# sheet3.net
KiCad netlist of a schematic drawn in Altium Designer
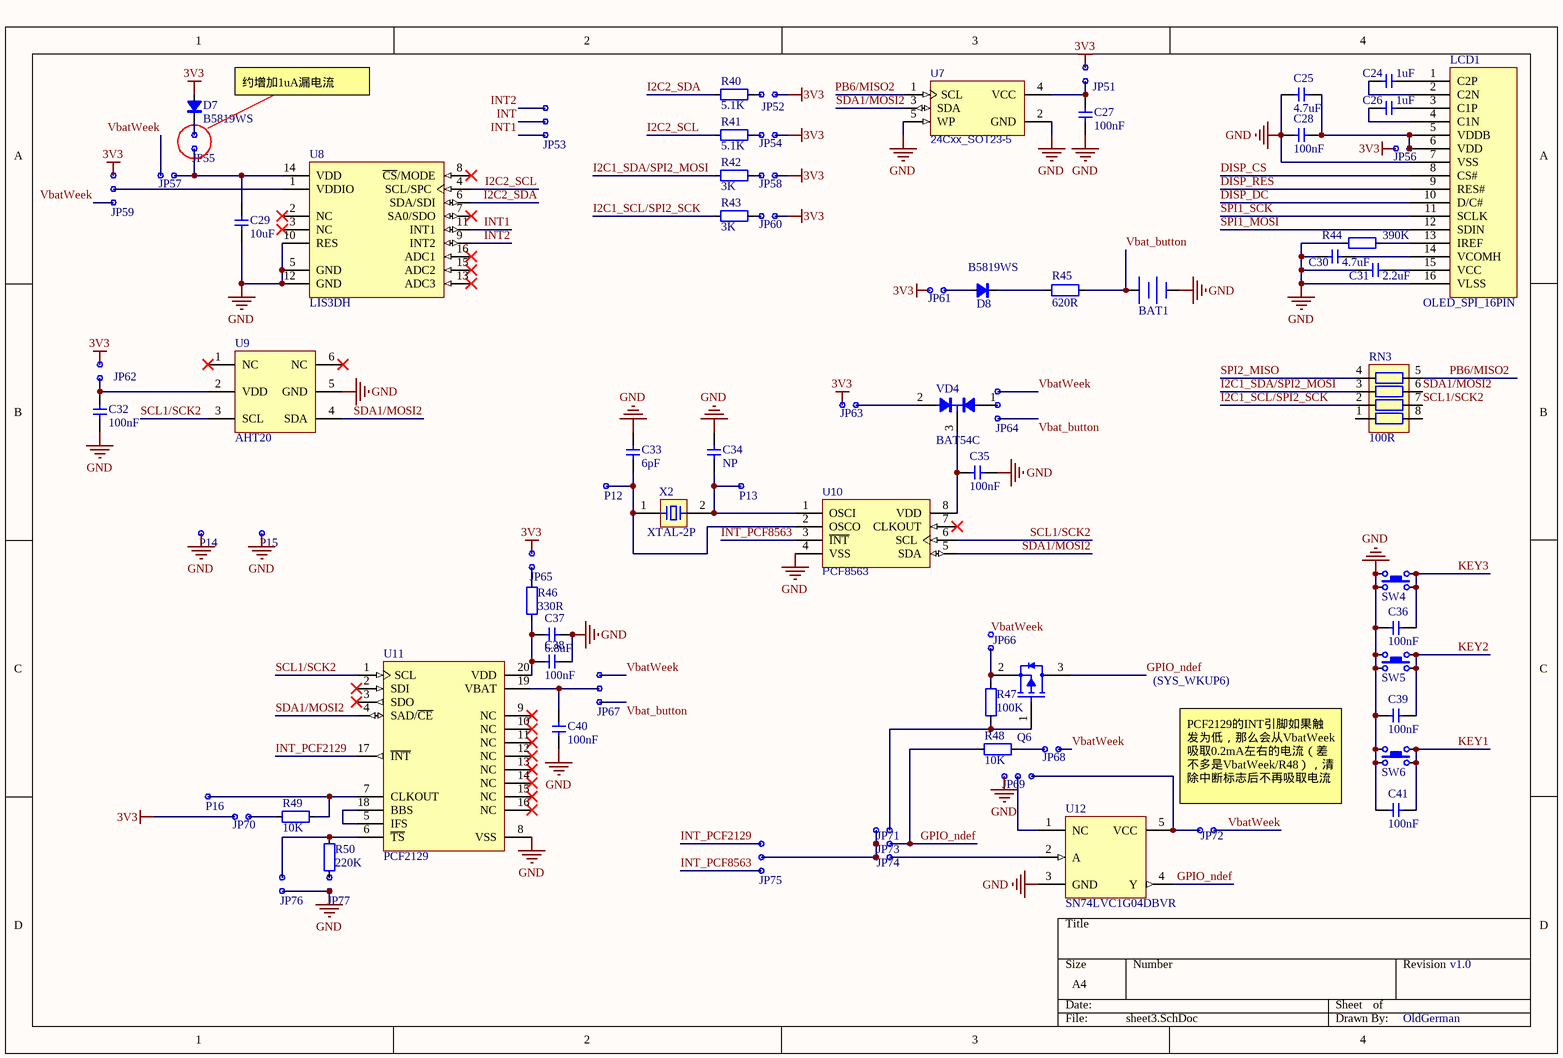
[diagram p0: sheet3.SchDoc]

(export (version "E")
  (design (tool "Eeschema 10.0.6"))
  (components
    (comp (ref "BAT1")
      (value "BAT")
      (footprint "MS621FE-FL11E")
      (description "锂电池")
      (libsource (lib "ODG_AD_Lib") (part "BAT"))
    )
    (comp (ref "C24")
      (value "1uF")
      (footprint "C0603")
      (description "Capacitor")
      (libsource (lib "ODG_AD_Lib") (part "CAP"))
    )
    (comp (ref "C25")
      (value "4.7uF")
      (footprint "C0603")
      (description "Capacitor")
      (libsource (lib "ODG_AD_Lib") (part "CAP"))
    )
    (comp (ref "C26")
      (value "1uF")
      (footprint "C0603")
      (description "Capacitor")
      (libsource (lib "ODG_AD_Lib") (part "CAP"))
    )
    (comp (ref "C27")
      (value "100nF")
      (footprint "C0603")
      (description "Capacitor")
      (libsource (lib "ODG_AD_Lib") (part "CAP"))
    )
    (comp (ref "C28")
      (value "100nF")
      (footprint "C0603")
      (description "Capacitor")
      (libsource (lib "ODG_AD_Lib") (part "CAP"))
    )
    (comp (ref "C29")
      (value "10uF")
      (footprint "C0603")
      (description "Capacitor")
      (libsource (lib "ODG_AD_Lib") (part "CAP"))
    )
    (comp (ref "C30")
      (value "4.7uF")
      (footprint "C0603")
      (description "Capacitor")
      (libsource (lib "ODG_AD_Lib") (part "CAP"))
    )
    (comp (ref "C31")
      (value "2.2uF")
      (footprint "C0603")
      (description "Capacitor")
      (libsource (lib "ODG_AD_Lib") (part "CAP"))
    )
    (comp (ref "C32")
      (value "100nF")
      (footprint "C0603")
      (description "Capacitor")
      (libsource (lib "ODG_AD_Lib") (part "CAP"))
    )
    (comp (ref "C33")
      (value "6pF")
      (footprint "C0603")
      (description "Capacitor")
      (libsource (lib "ODG_AD_Lib") (part "CAP"))
    )
    (comp (ref "C34")
      (value "NP")
      (footprint "C0603")
      (description "Capacitor")
      (libsource (lib "ODG_AD_Lib") (part "CAP"))
    )
    (comp (ref "C35")
      (value "100nF")
      (footprint "C0603")
      (description "Capacitor")
      (libsource (lib "ODG_AD_Lib") (part "CAP"))
    )
    (comp (ref "C36")
      (value "100nF")
      (footprint "C0603")
      (description "Capacitor")
      (libsource (lib "ODG_AD_Lib") (part "CAP"))
    )
    (comp (ref "C37")
      (value "6.8uF")
      (footprint "C0603")
      (description "Capacitor")
      (libsource (lib "ODG_AD_Lib") (part "CAP"))
    )
    (comp (ref "C38")
      (value "100nF")
      (footprint "C0603")
      (description "Capacitor")
      (libsource (lib "ODG_AD_Lib") (part "CAP"))
    )
    (comp (ref "C39")
      (value "100nF")
      (footprint "C0603")
      (description "Capacitor")
      (libsource (lib "ODG_AD_Lib") (part "CAP"))
    )
    (comp (ref "C40")
      (value "100nF")
      (footprint "C0603")
      (description "Capacitor")
      (libsource (lib "ODG_AD_Lib") (part "CAP"))
    )
    (comp (ref "C41")
      (value "100nF")
      (footprint "C0603")
      (description "Capacitor")
      (libsource (lib "ODG_AD_Lib") (part "CAP"))
    )
    (comp (ref "D7")
      (value "B5819WS")
      (footprint "SOD-323")
      (description "二极管")
      (libsource (lib "") (part "DIODE_1"))
    )
    (comp (ref "D8")
      (value "B5819WS")
      (footprint "SOD-323")
      (description "二极管")
      (libsource (lib "ODG_AD_Lib") (part "DIODE"))
    )
    (comp (ref "JP51")
      (value "CONN_X2_DOT")
      (footprint "2.54mm_Male_x2")
      (libsource (lib "ODG_AD_Lib") (part "CONN_X2_DOT"))
    )
    (comp (ref "JP52")
      (value "CONN_X2_DOT")
      (footprint "2.54mm_Male_x2")
      (libsource (lib "ODG_AD_Lib") (part "CONN_X2_DOT"))
    )
    (comp (ref "JP53")
      (value "CONN_X3_DOT")
      (footprint "2.54mm_Male_x3")
      (libsource (lib "ODG_AD_Lib") (part "CONN_X3_DOT"))
    )
    (comp (ref "JP54")
      (value "CONN_X2_DOT")
      (footprint "2.54mm_Male_x2")
      (libsource (lib "ODG_AD_Lib") (part "CONN_X2_DOT"))
    )
    (comp (ref "JP55")
      (value "CONN_X2_DOT")
      (footprint "2.54mm_Male_x2")
      (libsource (lib "ODG_AD_Lib") (part "CONN_X2_DOT"))
    )
    (comp (ref "JP56")
      (value "CONN_X2_DOT")
      (footprint "2.54mm_Male_x2")
      (libsource (lib "ODG_AD_Lib") (part "CONN_X2_DOT"))
    )
    (comp (ref "JP57")
      (value "CONN_X2_DOT")
      (footprint "2.54mm_Male_x2")
      (libsource (lib "ODG_AD_Lib") (part "CONN_X2_DOT"))
    )
    (comp (ref "JP58")
      (value "CONN_X2_DOT")
      (footprint "2.54mm_Male_x2")
      (libsource (lib "ODG_AD_Lib") (part "CONN_X2_DOT"))
    )
    (comp (ref "JP59")
      (value "CONN_X3_DOT")
      (footprint "2.54mm_Male_x3")
      (libsource (lib "ODG_AD_Lib") (part "CONN_X3_DOT"))
    )
    (comp (ref "JP60")
      (value "CONN_X2_DOT")
      (footprint "2.54mm_Male_x2")
      (libsource (lib "ODG_AD_Lib") (part "CONN_X2_DOT"))
    )
    (comp (ref "JP61")
      (value "CONN_X2_DOT")
      (footprint "2.54mm_Male_x2")
      (libsource (lib "ODG_AD_Lib") (part "CONN_X2_DOT"))
    )
    (comp (ref "JP62")
      (value "CONN_X2_DOT")
      (footprint "2.54mm_Male_x2")
      (libsource (lib "ODG_AD_Lib") (part "CONN_X2_DOT"))
    )
    (comp (ref "JP63")
      (value "CONN_X2_DOT")
      (footprint "2.54mm_Male_x2")
      (libsource (lib "ODG_AD_Lib") (part "CONN_X2_DOT"))
    )
    (comp (ref "JP64")
      (value "CONN_X3_DOT")
      (footprint "2.54mm_Male_x3")
      (libsource (lib "ODG_AD_Lib") (part "CONN_X3_DOT"))
    )
    (comp (ref "JP65")
      (value "CONN_X2_DOT")
      (footprint "2.54mm_Male_x2")
      (libsource (lib "ODG_AD_Lib") (part "CONN_X2_DOT"))
    )
    (comp (ref "JP66")
      (value "CONN_X2_DOT")
      (footprint "2.54mm_Male_x2")
      (libsource (lib "ODG_AD_Lib") (part "CONN_X2_DOT"))
    )
    (comp (ref "JP67")
      (value "CONN_X3_DOT")
      (footprint "2.54mm_Male_x3")
      (libsource (lib "ODG_AD_Lib") (part "CONN_X3_DOT"))
    )
    (comp (ref "JP68")
      (value "CONN_X2_DOT")
      (footprint "2.54mm_Male_x2")
      (libsource (lib "ODG_AD_Lib") (part "CONN_X2_DOT"))
    )
    (comp (ref "JP69")
      (value "CONN_X3_DOT")
      (footprint "2.54mm_Male_x3")
      (libsource (lib "ODG_AD_Lib") (part "CONN_X3_DOT"))
    )
    (comp (ref "JP70")
      (value "CONN_X2_DOT")
      (footprint "2.54mm_Male_x2")
      (libsource (lib "ODG_AD_Lib") (part "CONN_X2_DOT"))
    )
    (comp (ref "JP71")
      (value "CONN_X2_DOT")
      (footprint "2.54mm_Male_x2")
      (libsource (lib "ODG_AD_Lib") (part "CONN_X2_DOT"))
    )
    (comp (ref "JP72")
      (value "CONN_X2_DOT")
      (footprint "2.54mm_Male_x2")
      (libsource (lib "ODG_AD_Lib") (part "CONN_X2_DOT"))
    )
    (comp (ref "JP73")
      (value "CONN_X2_DOT")
      (footprint "2.54mm_Male_x2")
      (libsource (lib "ODG_AD_Lib") (part "CONN_X2_DOT"))
    )
    (comp (ref "JP74")
      (value "CONN_X2_DOT")
      (footprint "2.54mm_Male_x2")
      (libsource (lib "ODG_AD_Lib") (part "CONN_X2_DOT"))
    )
    (comp (ref "JP75")
      (value "CONN_X3_DOT")
      (footprint "2.54mm_Male_x3")
      (libsource (lib "ODG_AD_Lib") (part "CONN_X3_DOT"))
    )
    (comp (ref "JP76")
      (value "CONN_X2_DOT")
      (footprint "2.54mm_Male_x2")
      (libsource (lib "ODG_AD_Lib") (part "CONN_X2_DOT"))
    )
    (comp (ref "JP77")
      (value "CONN_X2_DOT")
      (footprint "2.54mm_Male_x2")
      (libsource (lib "ODG_AD_Lib") (part "CONN_X2_DOT"))
    )
    (comp (ref "LCD1")
      (value "OLED_SPI_16PIN")
      (footprint "oled_64x48_0.66_SSD1306_TOP_straight_no_3d")
      (libsource (lib "ODG_AD_Lib") (part "OLED_SPI_16PIN"))
    )
    (comp (ref "P12")
      (value "CONN_X1_DOT")
      (footprint "2.54mm_Male_x1")
      (libsource (lib "ODG_AD_Lib") (part "CONN_X1_DOT"))
    )
    (comp (ref "P13")
      (value "CONN_X1_DOT")
      (footprint "2.54mm_Male_x1")
      (libsource (lib "ODG_AD_Lib") (part "CONN_X1_DOT"))
    )
    (comp (ref "P14")
      (value "CONN_X1_DOT")
      (footprint "2.54mm_Male_x1")
      (libsource (lib "ODG_AD_Lib") (part "CONN_X1_DOT"))
    )
    (comp (ref "P15")
      (value "CONN_X1_DOT")
      (footprint "2.54mm_Male_x1")
      (libsource (lib "ODG_AD_Lib") (part "CONN_X1_DOT"))
    )
    (comp (ref "P16")
      (value "CONN_X1_DOT")
      (footprint "2.54mm_Male_x1")
      (libsource (lib "ODG_AD_Lib") (part "CONN_X1_DOT"))
    )
    (comp (ref "Q6")
      (value "P-MOS")
      (footprint "INFINEON SOT-23-3")
      (libsource (lib "ODG_AD_Lib") (part "P-MOS_123"))
    )
    (comp (ref "R40")
      (value "5.1K")
      (footprint "R0603")
      (description "Resistor")
      (libsource (lib "") (part "RES_1"))
    )
    (comp (ref "R41")
      (value "5.1K")
      (footprint "R0603")
      (description "Resistor")
      (libsource (lib "") (part "RES_1"))
    )
    (comp (ref "R42")
      (value "3K")
      (footprint "R0603")
      (description "Resistor")
      (libsource (lib "") (part "RES_1"))
    )
    (comp (ref "R43")
      (value "3K")
      (footprint "R0603")
      (description "Resistor")
      (libsource (lib "") (part "RES_1"))
    )
    (comp (ref "R44")
      (value "390K")
      (footprint "R0603")
      (description "Resistor")
      (libsource (lib "") (part "RES_2"))
    )
    (comp (ref "R45")
      (value "620R")
      (footprint "R0603")
      (description "Resistor")
      (libsource (lib "") (part "RES_2"))
    )
    (comp (ref "R46")
      (value "330R")
      (footprint "R0603")
      (description "Resistor")
      (libsource (lib "") (part "RES_3"))
    )
    (comp (ref "R47")
      (value "100K")
      (footprint "R0603")
      (description "Resistor")
      (libsource (lib "") (part "RES_2"))
    )
    (comp (ref "R48")
      (value "10K")
      (footprint "R0603")
      (description "Resistor")
      (libsource (lib "") (part "RES_1"))
    )
    (comp (ref "R49")
      (value "10K")
      (footprint "R0603")
      (description "Resistor")
      (libsource (lib "ODG_AD_Lib") (part "RES"))
    )
    (comp (ref "R50")
      (value "220K")
      (footprint "R0603")
      (description "Resistor")
      (libsource (lib "") (part "RES_3"))
    )
    (comp (ref "RN3")
      (value "100R")
      (footprint "RESNET 1206-8 CONCAVE")
      (description "贴片网络排阻")
      (fields (field (name "版权归属") "源创客"))
      (libsource (lib "ODG_AD_Lib") (part "RES-8P4R"))
    )
    (comp (ref "SW4")
      (value "Button-4P")
      (footprint "SWITCH_3X4X2.5_4PIN_SMD")
      (description "Button")
      (libsource (lib "ODG_AD_Lib") (part "Button-4P"))
    )
    (comp (ref "SW5")
      (value "Button-4P")
      (footprint "SWITCH_3X4X2.5_4PIN_SMD")
      (description "Button")
      (libsource (lib "ODG_AD_Lib") (part "Button-4P"))
    )
    (comp (ref "SW6")
      (value "Button-4P")
      (footprint "SWITCH_3X4X2.5_4PIN_SMD")
      (description "Button")
      (libsource (lib "ODG_AD_Lib") (part "Button-4P"))
    )
    (comp (ref "U7")
      (value "24Cxx_SOT23-5")
      (footprint "MICROCHIP SOT-23-5 OT")
      (libsource (lib "ODG_AD_Lib") (part "24Cxx_SOT23-5"))
    )
    (comp (ref "U8") (value "LIS3DH") (footprint "LGA-16-3X3") (libsource (lib "ODG_AD_Lib") (part "LIS3DH")))
    (comp (ref "U9")
      (value "AHT20")
      (footprint "AHT20")
      (description "线性稳压芯片")
      (fields (field (name "版权归属") "源创客"))
      (libsource (lib "ODG_AD_Lib") (part "AHT20"))
    )
    (comp (ref "U10")
      (value "PCF8563")
      (footprint "ANALOG DEV SOIC-8 R8")
      (libsource (lib "ODG_AD_Lib") (part "PCF8563"))
    )
    (comp (ref "U11")
      (value "PCF2129")
      (footprint "NXP_SO20")
      (description "RTC")
      (libsource (lib "ODG_AD_Lib") (part "PCF2129"))
    )
    (comp (ref "U12")
      (value "SN74LVC1G04DBVR")
      (footprint "TI SOT-23-5 DBV")
      (description "IC GATE NOT")
      (libsource (lib "ODG_AD_Lib") (part "SN74LVC1G04DBVR"))
    )
    (comp (ref "VD4")
      (value "BAT54C")
      (footprint "INFINEON SOT-23-3")
      (description "贴片肖特基二极管")
      (fields (field (name "版权归属") "源创客"))
      (libsource (lib "ODG_AD_Lib") (part "BAT54C"))
    )
    (comp (ref "X2")
      (value "XTAL-2P")
      (footprint "XTAL_2P_3215")
      (description "2脚无源石英晶振")
      (fields (field (name "版权归属") "源创客"))
      (libsource (lib "ODG_AD_Lib") (part "XTAL-2P"))
    )
  )
  (nets
    (net (code "1") (name "/DISP_CS") (class "Default")
      (node (ref "LCD1") (pin "8") (pinfunction "CS#_8") (pintype "passive"))
    )
    (net (code "2") (name "/DISP_DC") (class "Default")
      (node (ref "LCD1") (pin "10") (pinfunction "D/C#_10") (pintype "passive"))
    )
    (net (code "3") (name "/DISP_RES") (class "Default")
      (node (ref "LCD1") (pin "9") (pinfunction "RES#_9") (pintype "passive"))
    )
    (net (code "4") (name "/GPIO_ndef") (class "Default")
      (node (ref "JP73") (pin "2") (pinfunction "2_2") (pintype "passive"))
      (node (ref "Q6") (pin "3") (pinfunction "D_3") (pintype "passive"))
      (node (ref "R48") (pin "2") (pinfunction "2_2") (pintype "passive"))
      (node (ref "U12") (pin "4") (pinfunction "Y_4") (pintype "output"))
    )
    (net (code "5") (name "/I2C1_SCL{slash}SPI2_SCK") (class "Default")
      (node (ref "R43") (pin "2") (pinfunction "2_2") (pintype "passive"))
      (node (ref "RN3") (pin "2") (pinfunction "2_2") (pintype "passive"))
    )
    (net (code "6") (name "/I2C1_SDA{slash}SPI2_MOSI") (class "Default")
      (node (ref "R42") (pin "2") (pinfunction "2_2") (pintype "passive"))
      (node (ref "RN3") (pin "3") (pinfunction "3_3") (pintype "passive"))
    )
    (net (code "7") (name "/I2C2_SCL") (class "Default")
      (node (ref "R41") (pin "2") (pinfunction "2_2") (pintype "passive"))
      (node (ref "U8") (pin "4") (pinfunction "SCL/SPC_4") (pintype "input"))
    )
    (net (code "8") (name "/I2C2_SDA") (class "Default")
      (node (ref "R40") (pin "2") (pinfunction "2_2") (pintype "passive"))
      (node (ref "U8") (pin "6") (pinfunction "SDA/SDI_6") (pintype "bidirectional"))
    )
    (net (code "9") (name "/INT") (class "Default")
      (node (ref "JP53") (pin "2") (pinfunction "2_2") (pintype "passive"))
    )
    (net (code "10") (name "/INT1") (class "Default")
      (node (ref "JP53") (pin "3") (pinfunction "3_3") (pintype "passive"))
      (node (ref "U8") (pin "11") (pinfunction "INT1_11") (pintype "bidirectional"))
    )
    (net (code "11") (name "/INT2") (class "Default")
      (node (ref "JP53") (pin "1") (pinfunction "1_1") (pintype "passive"))
      (node (ref "U8") (pin "9") (pinfunction "INT2_9") (pintype "bidirectional"))
    )
    (net (code "12") (name "/INT_PCF2129") (class "Default")
      (node (ref "JP75") (pin "1") (pinfunction "1_1") (pintype "passive"))
      (node (ref "U11") (pin "17") (pinfunction "~{INT}_17") (pintype "output"))
    )
    (net (code "13") (name "/INT_PCF8563") (class "Default")
      (node (ref "JP75") (pin "3") (pinfunction "3_3") (pintype "passive"))
      (node (ref "U10") (pin "3") (pinfunction "~{INT}_3") (pintype "passive"))
    )
    (net (code "14") (name "/KEY1") (class "Default")
      (node (ref "C41") (pin "2") (pinfunction "2_2") (pintype "passive"))
      (node (ref "SW6") (pin "3") (pinfunction "3_3") (pintype "passive"))
      (node (ref "SW6") (pin "4") (pinfunction "4_4") (pintype "passive"))
    )
    (net (code "15") (name "/KEY2") (class "Default")
      (node (ref "C39") (pin "2") (pinfunction "2_2") (pintype "passive"))
      (node (ref "SW5") (pin "3") (pinfunction "3_3") (pintype "passive"))
      (node (ref "SW5") (pin "4") (pinfunction "4_4") (pintype "passive"))
    )
    (net (code "16") (name "/KEY3") (class "Default")
      (node (ref "C36") (pin "2") (pinfunction "2_2") (pintype "passive"))
      (node (ref "SW4") (pin "3") (pinfunction "3_3") (pintype "passive"))
      (node (ref "SW4") (pin "4") (pinfunction "4_4") (pintype "passive"))
    )
    (net (code "17") (name "/PB6{slash}MISO2") (class "Default")
      (node (ref "RN3") (pin "5") (pinfunction "5_5") (pintype "passive"))
      (node (ref "U7") (pin "1") (pinfunction "SCL_1") (pintype "input"))
    )
    (net (code "18") (name "/SCL1{slash}SCK2") (class "Default")
      (node (ref "RN3") (pin "7") (pinfunction "7_7") (pintype "passive"))
      (node (ref "U10") (pin "6") (pinfunction "SCL_6") (pintype "input"))
      (node (ref "U11") (pin "1") (pinfunction "SCL_1") (pintype "input"))
      (node (ref "U9") (pin "3") (pinfunction "SCL_3") (pintype "passive"))
    )
    (net (code "19") (name "/SDA1{slash}MOSI2") (class "Default")
      (node (ref "RN3") (pin "6") (pinfunction "6_6") (pintype "passive"))
      (node (ref "U10") (pin "5") (pinfunction "SDA_5") (pintype "bidirectional"))
      (node (ref "U11") (pin "4") (pinfunction "SAD/~{CE}_4") (pintype "bidirectional"))
      (node (ref "U7") (pin "3") (pinfunction "SDA_3") (pintype "bidirectional"))
      (node (ref "U9") (pin "4") (pinfunction "SDA_4") (pintype "passive"))
    )
    (net (code "20") (name "/SPI1_MOSI") (class "Default")
      (node (ref "LCD1") (pin "12") (pinfunction "SDIN_12") (pintype "passive"))
    )
    (net (code "21") (name "/SPI1_SCK") (class "Default")
      (node (ref "LCD1") (pin "11") (pinfunction "SCLK_11") (pintype "passive"))
    )
    (net (code "22") (name "/SPI2_MISO") (class "Default")
      (node (ref "RN3") (pin "4") (pinfunction "4_4") (pintype "passive"))
    )
    (net (code "23") (name "/VbatWeek") (class "Default")
      (node (ref "JP57") (pin "1") (pinfunction "1_1") (pintype "passive"))
      (node (ref "JP59") (pin "3") (pinfunction "3_3") (pintype "passive"))
      (node (ref "JP64") (pin "1") (pinfunction "1_1") (pintype "passive"))
      (node (ref "JP66") (pin "1") (pinfunction "1_1") (pintype "passive"))
      (node (ref "JP67") (pin "1") (pinfunction "1_1") (pintype "passive"))
      (node (ref "JP68") (pin "2") (pinfunction "2_2") (pintype "passive"))
      (node (ref "JP72") (pin "2") (pinfunction "2_2") (pintype "passive"))
    )
    (net (code "24") (name "/Vbat_button") (class "Default")
      (node (ref "BAT1") (pin "1") (pinfunction "+_1") (pintype "passive"))
      (node (ref "JP64") (pin "3") (pinfunction "3_3") (pintype "passive"))
      (node (ref "JP67") (pin "3") (pinfunction "3_3") (pintype "passive"))
      (node (ref "R45") (pin "2") (pinfunction "2_2") (pintype "passive"))
    )
    (net (code "25") (name "3V3") (class "Default")
      (node (ref "D7") (pin "1") (pinfunction "A_1") (pintype "passive"))
      (node (ref "JP51") (pin "1") (pinfunction "1_1") (pintype "passive"))
      (node (ref "JP52") (pin "2") (pinfunction "2_2") (pintype "passive"))
      (node (ref "JP54") (pin "2") (pinfunction "2_2") (pintype "passive"))
      (node (ref "JP56") (pin "1") (pinfunction "1_1") (pintype "passive"))
      (node (ref "JP58") (pin "2") (pinfunction "2_2") (pintype "passive"))
      (node (ref "JP59") (pin "1") (pinfunction "1_1") (pintype "passive"))
      (node (ref "JP60") (pin "2") (pinfunction "2_2") (pintype "passive"))
      (node (ref "JP61") (pin "1") (pinfunction "1_1") (pintype "passive"))
      (node (ref "JP62") (pin "1") (pinfunction "1_1") (pintype "passive"))
      (node (ref "JP63") (pin "1") (pinfunction "1_1") (pintype "passive"))
      (node (ref "JP65") (pin "1") (pinfunction "1_1") (pintype "passive"))
      (node (ref "JP70") (pin "1") (pinfunction "1_1") (pintype "passive"))
    )
    (net (code "26") (name "GND") (class "Default")
      (node (ref "BAT1") (pin "2") (pinfunction "-_2") (pintype "passive"))
      (node (ref "C25") (pin "2") (pinfunction "2_2") (pintype "passive"))
      (node (ref "C27") (pin "2") (pinfunction "2_2") (pintype "passive"))
      (node (ref "C28") (pin "1") (pinfunction "1_1") (pintype "passive"))
      (node (ref "C29") (pin "2") (pinfunction "2_2") (pintype "passive"))
      (node (ref "C30") (pin "2") (pinfunction "2_2") (pintype "passive"))
      (node (ref "C31") (pin "2") (pinfunction "2_2") (pintype "passive"))
      (node (ref "C32") (pin "2") (pinfunction "2_2") (pintype "passive"))
      (node (ref "C33") (pin "1") (pinfunction "1_1") (pintype "passive"))
      (node (ref "C34") (pin "1") (pinfunction "1_1") (pintype "passive"))
      (node (ref "C35") (pin "2") (pinfunction "2_2") (pintype "passive"))
      (node (ref "C36") (pin "1") (pinfunction "1_1") (pintype "passive"))
      (node (ref "C37") (pin "2") (pinfunction "2_2") (pintype "passive"))
      (node (ref "C38") (pin "2") (pinfunction "2_2") (pintype "passive"))
      (node (ref "C39") (pin "1") (pinfunction "1_1") (pintype "passive"))
      (node (ref "C40") (pin "2") (pinfunction "2_2") (pintype "passive"))
      (node (ref "C41") (pin "1") (pinfunction "1_1") (pintype "passive"))
      (node (ref "JP69") (pin "1") (pinfunction "1_1") (pintype "passive"))
      (node (ref "JP76") (pin "2") (pinfunction "2_2") (pintype "passive"))
      (node (ref "JP77") (pin "2") (pinfunction "2_2") (pintype "passive"))
      (node (ref "LCD1") (pin "16") (pinfunction "VLSS_16") (pintype "passive"))
      (node (ref "LCD1") (pin "7") (pinfunction "VSS_7") (pintype "passive"))
      (node (ref "P14") (pin "1") (pinfunction "1_1") (pintype "passive"))
      (node (ref "P15") (pin "1") (pinfunction "1_1") (pintype "passive"))
      (node (ref "R44") (pin "1") (pinfunction "1_1") (pintype "passive"))
      (node (ref "SW4") (pin "1") (pinfunction "1_1") (pintype "passive"))
      (node (ref "SW4") (pin "2") (pinfunction "2_2") (pintype "passive"))
      (node (ref "SW5") (pin "1") (pinfunction "1_1") (pintype "passive"))
      (node (ref "SW5") (pin "2") (pinfunction "2_2") (pintype "passive"))
      (node (ref "SW6") (pin "1") (pinfunction "1_1") (pintype "passive"))
      (node (ref "SW6") (pin "2") (pinfunction "2_2") (pintype "passive"))
      (node (ref "U10") (pin "4") (pinfunction "VSS_4") (pintype "passive"))
      (node (ref "U11") (pin "8") (pinfunction "VSS_8") (pintype "power_in"))
      (node (ref "U12") (pin "3") (pinfunction "GND_3") (pintype "power_in"))
      (node (ref "U7") (pin "2") (pinfunction "GND_2") (pintype "passive"))
      (node (ref "U7") (pin "5") (pinfunction "WP_5") (pintype "input"))
      (node (ref "U8") (pin "10") (pinfunction "RES_10") (pintype "power_in"))
      (node (ref "U8") (pin "12") (pinfunction "GND_12") (pintype "power_in"))
      (node (ref "U8") (pin "5") (pinfunction "GND_5") (pintype "power_in"))
      (node (ref "U9") (pin "5") (pinfunction "GND_5") (pintype "passive"))
    )
    (net (code "27") (name "Net-(D7-C)") (class "Default")
      (node (ref "D7") (pin "2") (pinfunction "C_2") (pintype "passive"))
      (node (ref "JP55") (pin "1") (pinfunction "1_1") (pintype "passive"))
    )
    (net (code "28") (name "Net-(D8-A)") (class "Default")
      (node (ref "D8") (pin "1") (pinfunction "A_1") (pintype "passive"))
      (node (ref "JP61") (pin "2") (pinfunction "2_2") (pintype "passive"))
    )
    (net (code "29") (name "Net-(D8-C)") (class "Default")
      (node (ref "D8") (pin "2") (pinfunction "C_2") (pintype "passive"))
      (node (ref "R45") (pin "1") (pinfunction "1_1") (pintype "passive"))
    )
    (net (code "30") (name "Net-(JP52-Pad1)") (class "Default")
      (node (ref "JP52") (pin "1") (pinfunction "1_1") (pintype "passive"))
      (node (ref "R40") (pin "1") (pinfunction "1_1") (pintype "passive"))
    )
    (net (code "31") (name "Net-(JP54-Pad1)") (class "Default")
      (node (ref "JP54") (pin "1") (pinfunction "1_1") (pintype "passive"))
      (node (ref "R41") (pin "1") (pinfunction "1_1") (pintype "passive"))
    )
    (net (code "32") (name "Net-(JP58-Pad1)") (class "Default")
      (node (ref "JP58") (pin "1") (pinfunction "1_1") (pintype "passive"))
      (node (ref "R42") (pin "1") (pinfunction "1_1") (pintype "passive"))
    )
    (net (code "33") (name "Net-(JP60-Pad1)") (class "Default")
      (node (ref "JP60") (pin "1") (pinfunction "1_1") (pintype "passive"))
      (node (ref "R43") (pin "1") (pinfunction "1_1") (pintype "passive"))
    )
    (net (code "34") (name "Net-(JP63-Pad2)") (class "Default")
      (node (ref "JP63") (pin "2") (pinfunction "2_2") (pintype "passive"))
      (node (ref "VD4") (pin "2") (pinfunction "2_2") (pintype "passive"))
    )
    (net (code "35") (name "Net-(JP64-Pad2)") (class "Default")
      (node (ref "JP64") (pin "2") (pinfunction "2_2") (pintype "passive"))
      (node (ref "VD4") (pin "1") (pinfunction "1_1") (pintype "passive"))
    )
    (net (code "36") (name "Net-(JP65-Pad2)") (class "Default")
      (node (ref "JP65") (pin "2") (pinfunction "2_2") (pintype "passive"))
      (node (ref "R46") (pin "2") (pinfunction "2_2") (pintype "passive"))
    )
    (net (code "37") (name "Net-(JP68-Pad1)") (class "Default")
      (node (ref "JP68") (pin "1") (pinfunction "1_1") (pintype "passive"))
      (node (ref "R48") (pin "1") (pinfunction "1_1") (pintype "passive"))
    )
    (net (code "38") (name "Net-(JP70-Pad2)") (class "Default")
      (node (ref "JP70") (pin "2") (pinfunction "2_2") (pintype "passive"))
      (node (ref "R49") (pin "2") (pinfunction "2_2") (pintype "passive"))
    )
    (net (code "39") (name "Net-(JP71-Pad1)") (class "Default")
      (node (ref "JP71") (pin "1") (pinfunction "1_1") (pintype "passive"))
      (node (ref "JP73") (pin "1") (pinfunction "1_1") (pintype "passive"))
      (node (ref "JP74") (pin "1") (pinfunction "1_1") (pintype "passive"))
      (node (ref "JP75") (pin "2") (pinfunction "2_2") (pintype "passive"))
    )
    (net (code "40") (name "Net-(JP77-Pad1)") (class "Default")
      (node (ref "JP77") (pin "1") (pinfunction "1_1") (pintype "passive"))
      (node (ref "R50") (pin "1") (pinfunction "1_1") (pintype "passive"))
    )
    (net (code "41") (name "Net-(LCD1-C1N)") (class "Default")
      (node (ref "C26") (pin "2") (pinfunction "2_2") (pintype "passive"))
      (node (ref "LCD1") (pin "4") (pinfunction "C1N_4") (pintype "passive"))
    )
    (net (code "42") (name "Net-(LCD1-C1P)") (class "Default")
      (node (ref "C26") (pin "1") (pinfunction "1_1") (pintype "passive"))
      (node (ref "LCD1") (pin "3") (pinfunction "C1P_3") (pintype "passive"))
    )
    (net (code "43") (name "Net-(LCD1-C2N)") (class "Default")
      (node (ref "C24") (pin "2") (pinfunction "2_2") (pintype "passive"))
      (node (ref "LCD1") (pin "2") (pinfunction "C2N_2") (pintype "passive"))
    )
    (net (code "44") (name "Net-(LCD1-C2P)") (class "Default")
      (node (ref "C24") (pin "1") (pinfunction "1_1") (pintype "passive"))
      (node (ref "LCD1") (pin "1") (pinfunction "C2P_1") (pintype "passive"))
    )
    (net (code "45") (name "Net-(LCD1-IREF)") (class "Default")
      (node (ref "LCD1") (pin "13") (pinfunction "IREF_13") (pintype "passive"))
      (node (ref "R44") (pin "2") (pinfunction "2_2") (pintype "passive"))
    )
    (net (code "46") (name "Net-(LCD1-VCC)") (class "Default")
      (node (ref "C31") (pin "1") (pinfunction "1_1") (pintype "passive"))
      (node (ref "LCD1") (pin "15") (pinfunction "VCC_15") (pintype "passive"))
    )
    (net (code "47") (name "Net-(LCD1-VCOMH)") (class "Default")
      (node (ref "C30") (pin "1") (pinfunction "1_1") (pintype "passive"))
      (node (ref "LCD1") (pin "14") (pinfunction "VCOMH_14") (pintype "passive"))
    )
    (net (code "48") (name "Net-(LCD1-VDD)") (class "Default")
      (node (ref "C25") (pin "1") (pinfunction "1_1") (pintype "passive"))
      (node (ref "C28") (pin "2") (pinfunction "2_2") (pintype "passive"))
      (node (ref "JP56") (pin "2") (pinfunction "2_2") (pintype "passive"))
      (node (ref "LCD1") (pin "5") (pinfunction "VDDB_5") (pintype "passive"))
      (node (ref "LCD1") (pin "6") (pinfunction "VDD_6") (pintype "passive"))
    )
    (net (code "49") (name "Net-(Q6-G)") (class "Default")
      (node (ref "JP71") (pin "2") (pinfunction "2_2") (pintype "passive"))
      (node (ref "Q6") (pin "1") (pinfunction "G_1") (pintype "passive"))
      (node (ref "R47") (pin "1") (pinfunction "1_1") (pintype "passive"))
    )
    (net (code "50") (name "Net-(Q6-S)") (class "Default")
      (node (ref "JP66") (pin "2") (pinfunction "2_2") (pintype "passive"))
      (node (ref "Q6") (pin "2") (pinfunction "S_2") (pintype "passive"))
      (node (ref "R47") (pin "2") (pinfunction "2_2") (pintype "passive"))
    )
    (net (code "51") (name "Net-(U7-VCC)") (class "Default")
      (node (ref "C27") (pin "1") (pinfunction "1_1") (pintype "passive"))
      (node (ref "JP51") (pin "2") (pinfunction "2_2") (pintype "passive"))
      (node (ref "U7") (pin "4") (pinfunction "VCC_4") (pintype "passive"))
    )
    (net (code "52") (name "Net-(U8-VDD)") (class "Default")
      (node (ref "C29") (pin "1") (pinfunction "1_1") (pintype "passive"))
      (node (ref "JP55") (pin "2") (pinfunction "2_2") (pintype "passive"))
      (node (ref "JP57") (pin "2") (pinfunction "2_2") (pintype "passive"))
      (node (ref "U8") (pin "14") (pinfunction "VDD_14") (pintype "power_in"))
    )
    (net (code "53") (name "Net-(U8-VDDIO)") (class "Default")
      (node (ref "JP59") (pin "2") (pinfunction "2_2") (pintype "passive"))
      (node (ref "U8") (pin "1") (pinfunction "VDDIO_1") (pintype "power_in"))
    )
    (net (code "54") (name "Net-(U9-VDD)") (class "Default")
      (node (ref "C32") (pin "1") (pinfunction "1_1") (pintype "passive"))
      (node (ref "JP62") (pin "2") (pinfunction "2_2") (pintype "passive"))
      (node (ref "U9") (pin "2") (pinfunction "VDD_2") (pintype "passive"))
    )
    (net (code "55") (name "Net-(U10-OSCI)") (class "Default")
      (node (ref "C34") (pin "2") (pinfunction "2_2") (pintype "passive"))
      (node (ref "P13") (pin "1") (pinfunction "1_1") (pintype "passive"))
      (node (ref "U10") (pin "1") (pinfunction "OSCI_1") (pintype "passive"))
      (node (ref "X2") (pin "2") (pinfunction "2_2") (pintype "passive"))
    )
    (net (code "56") (name "Net-(U10-OSCO)") (class "Default")
      (node (ref "C33") (pin "2") (pinfunction "2_2") (pintype "passive"))
      (node (ref "P12") (pin "1") (pinfunction "1_1") (pintype "passive"))
      (node (ref "U10") (pin "2") (pinfunction "OSCO_2") (pintype "passive"))
      (node (ref "X2") (pin "1") (pinfunction "1_1") (pintype "passive"))
    )
    (net (code "57") (name "Net-(U10-VDD)") (class "Default")
      (node (ref "C35") (pin "1") (pinfunction "1_1") (pintype "passive"))
      (node (ref "U10") (pin "8") (pinfunction "VDD_8") (pintype "passive"))
      (node (ref "VD4") (pin "3") (pinfunction "3_3") (pintype "passive"))
    )
    (net (code "58") (name "Net-(U11-BBS)") (class "Default")
      (node (ref "U11") (pin "18") (pinfunction "BBS_18") (pintype "power_in"))
      (node (ref "U11") (pin "5") (pinfunction "IFS_5") (pintype "power_in"))
    )
    (net (code "59") (name "Net-(U11-CLKOUT)") (class "Default")
      (node (ref "P16") (pin "1") (pinfunction "1_1") (pintype "passive"))
      (node (ref "R49") (pin "1") (pinfunction "1_1") (pintype "passive"))
      (node (ref "U11") (pin "7") (pinfunction "CLKOUT_7") (pintype "power_in"))
    )
    (net (code "60") (name "Net-(U11-VBAT)") (class "Default")
      (node (ref "C40") (pin "1") (pinfunction "1_1") (pintype "passive"))
      (node (ref "JP67") (pin "2") (pinfunction "2_2") (pintype "passive"))
      (node (ref "U11") (pin "19") (pinfunction "VBAT_19") (pintype "power_in"))
    )
    (net (code "61") (name "Net-(U11-VDD)") (class "Default")
      (node (ref "C37") (pin "1") (pinfunction "1_1") (pintype "passive"))
      (node (ref "C38") (pin "1") (pinfunction "1_1") (pintype "passive"))
      (node (ref "R46") (pin "1") (pinfunction "1_1") (pintype "passive"))
      (node (ref "U11") (pin "20") (pinfunction "VDD_20") (pintype "power_in"))
    )
    (net (code "62") (name "Net-(U11-~{TS})") (class "Default")
      (node (ref "JP76") (pin "1") (pinfunction "1_1") (pintype "passive"))
      (node (ref "R50") (pin "2") (pinfunction "2_2") (pintype "passive"))
      (node (ref "U11") (pin "6") (pinfunction "~{TS}_6") (pintype "power_in"))
    )
    (net (code "63") (name "Net-(U12-A)") (class "Default")
      (node (ref "JP74") (pin "2") (pinfunction "2_2") (pintype "passive"))
      (node (ref "U12") (pin "2") (pinfunction "A_2") (pintype "input"))
    )
    (net (code "64") (name "Net-(U12-NC)") (class "Default")
      (node (ref "JP69") (pin "2") (pinfunction "2_2") (pintype "passive"))
      (node (ref "U12") (pin "1") (pinfunction "NC_1") (pintype "passive"))
    )
    (net (code "65") (name "Net-(U12-VCC)") (class "Default")
      (node (ref "JP69") (pin "3") (pinfunction "3_3") (pintype "passive"))
      (node (ref "JP72") (pin "1") (pinfunction "1_1") (pintype "passive"))
      (node (ref "U12") (pin "5") (pinfunction "VCC_5") (pintype "passive"))
    )
    (net (code "66") (name "unconnected-(RN3-Pad1)") (class "Default")
      (node (ref "RN3") (pin "1") (pinfunction "1_1") (pintype "passive"))
    )
    (net (code "67") (name "unconnected-(RN3-Pad8)") (class "Default")
      (node (ref "RN3") (pin "8") (pinfunction "8_8") (pintype "passive"))
    )
    (net (code "68") (name "unconnected-(U8-ADC1-Pad16)") (class "Default")
      (node (ref "U8") (pin "16") (pinfunction "ADC1_16") (pintype "input+no_connect"))
    )
    (net (code "69") (name "unconnected-(U8-ADC2-Pad15)") (class "Default")
      (node (ref "U8") (pin "15") (pinfunction "ADC2_15") (pintype "input+no_connect"))
    )
    (net (code "70") (name "unconnected-(U8-ADC3-Pad13)") (class "Default")
      (node (ref "U8") (pin "13") (pinfunction "ADC3_13") (pintype "input+no_connect"))
    )
    (net (code "71") (name "unconnected-(U8-NC-Pad2)") (class "Default")
      (node (ref "U8") (pin "2") (pinfunction "NC_2") (pintype "power_in+no_connect"))
    )
    (net (code "72") (name "unconnected-(U8-NC-Pad3)") (class "Default")
      (node (ref "U8") (pin "3") (pinfunction "NC_3") (pintype "power_in+no_connect"))
    )
    (net (code "73") (name "unconnected-(U8-SA0{slash}SDO-Pad7)") (class "Default")
      (node (ref "U8") (pin "7") (pinfunction "SA0/SDO_7") (pintype "bidirectional+no_connect"))
    )
    (net (code "74") (name "unconnected-(U8-~{CS}{slash}MODE-Pad8)") (class "Default")
      (node (ref "U8") (pin "8") (pinfunction "~{CS}/MODE_8") (pintype "input+no_connect"))
    )
    (net (code "75") (name "unconnected-(U9-NC-Pad1)") (class "Default")
      (node (ref "U9") (pin "1") (pinfunction "NC_1") (pintype "passive+no_connect"))
    )
    (net (code "76") (name "unconnected-(U9-NC-Pad6)") (class "Default")
      (node (ref "U9") (pin "6") (pinfunction "NC_6") (pintype "passive+no_connect"))
    )
    (net (code "77") (name "unconnected-(U10-CLKOUT-Pad7)") (class "Default")
      (node (ref "U10") (pin "7") (pinfunction "CLKOUT_7") (pintype "input+no_connect"))
    )
    (net (code "78") (name "unconnected-(U11-NC-Pad9)") (class "Default")
      (node (ref "U11") (pin "9") (pinfunction "NC_9") (pintype "power_in+no_connect"))
    )
    (net (code "79") (name "unconnected-(U11-NC-Pad10)") (class "Default")
      (node (ref "U11") (pin "10") (pinfunction "NC_10") (pintype "power_in+no_connect"))
    )
    (net (code "80") (name "unconnected-(U11-NC-Pad11)") (class "Default")
      (node (ref "U11") (pin "11") (pinfunction "NC_11") (pintype "power_in+no_connect"))
    )
    (net (code "81") (name "unconnected-(U11-NC-Pad12)") (class "Default")
      (node (ref "U11") (pin "12") (pinfunction "NC_12") (pintype "power_in+no_connect"))
    )
    (net (code "82") (name "unconnected-(U11-NC-Pad13)") (class "Default")
      (node (ref "U11") (pin "13") (pinfunction "NC_13") (pintype "power_in+no_connect"))
    )
    (net (code "83") (name "unconnected-(U11-NC-Pad14)") (class "Default")
      (node (ref "U11") (pin "14") (pinfunction "NC_14") (pintype "power_in+no_connect"))
    )
    (net (code "84") (name "unconnected-(U11-NC-Pad15)") (class "Default")
      (node (ref "U11") (pin "15") (pinfunction "NC_15") (pintype "power_in+no_connect"))
    )
    (net (code "85") (name "unconnected-(U11-NC-Pad16)") (class "Default")
      (node (ref "U11") (pin "16") (pinfunction "NC_16") (pintype "power_in+no_connect"))
    )
    (net (code "86") (name "unconnected-(U11-SDI-Pad2)") (class "Default")
      (node (ref "U11") (pin "2") (pinfunction "SDI_2") (pintype "input+no_connect"))
    )
    (net (code "87") (name "unconnected-(U11-SDO-Pad3)") (class "Default")
      (node (ref "U11") (pin "3") (pinfunction "SDO_3") (pintype "output+no_connect"))
    )
  )
)
